# PowerMeter_Peripherics.net
KiCad netlist of a schematic drawn in Altium Designer
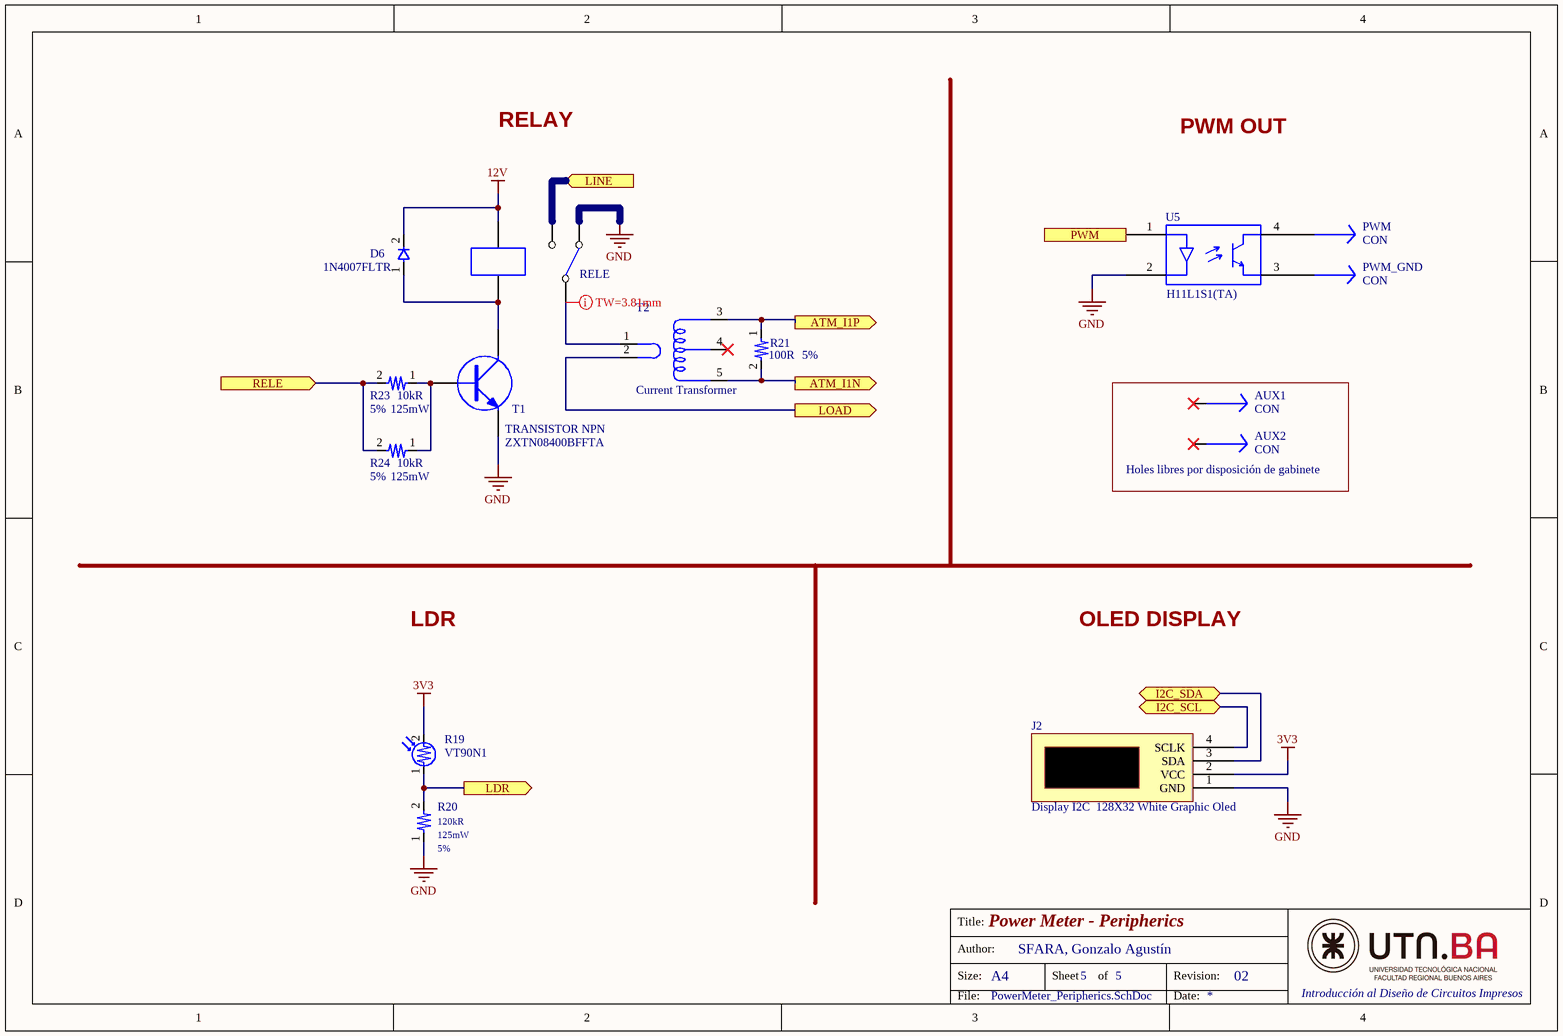
[diagram p0: PowerMeter_Peripherics.SchDoc]

(export (version "E")
  (design (tool "Eeschema 10.0.6"))
  (components
    (comp (ref "AUX1")
      (value "CON")
      (footprint "HOLE 1.3")
      (description "Hole")
      (libsource (lib "PowerMeter") (part "CON"))
    )
    (comp (ref "AUX2")
      (value "CON")
      (footprint "HOLE 1.3")
      (description "Hole")
      (libsource (lib "PowerMeter") (part "CON"))
    )
    (comp (ref "D6")
      (value "Standard Rectifier 1000V SOD-123")
      (footprint "SOD_123")
      (fields
        (field (name "MANUFACTURER") "Sangdest Microelectronics")
        (field (name "MANUFACTURER PART NUMBER") "1N4007FLTR")
      )
      (libsource (lib "PowerMeter") (part "DIODE"))
    )
    (comp (ref "J2")
      (value "Display I2C  128X32 White Graphic Oled")
      (footprint "SSD1306")
      (description "128X32 White Graphic Oled")
      (fields
        (field (name "MANUFACTURER") "Focus LCDs")
        (field (name "MANUFACTURER PART NUMBER") "O12832A-GW-TW3")
      )
      (libsource (lib "PowerMeter") (part "Display I2C"))
    )
    (comp (ref "PWM")
      (value "CON")
      (footprint "HOLE 1.3")
      (description "Hole")
      (libsource (lib "PowerMeter") (part "CON"))
    )
    (comp (ref "PWM_GND")
      (value "CON")
      (footprint "HOLE 1.3")
      (description "Hole")
      (libsource (lib "PowerMeter") (part "CON"))
    )
    (comp (ref "R19")
      (value "LDR 200 Kohm, 80MW")
      (footprint "LDR")
      (description "200 Kohm, 80MW")
      (fields (field (name "MANUFACTURER") "Excelitas") (field (name "MANUFACTURER PART NUMBER") "VT90N1"))
      (libsource (lib "PowerMeter") (part "LDR"))
    )
    (comp (ref "R20")
      (value "RES 120kOhm 5% 1/8W")
      (footprint "R_0805")
      (description "Chip Resistor Automotive Grade Thick Film 0805 120kOhm 5% Paper T/R")
      (fields
        (field (name "MANUFACTURER") "Yageo")
        (field (name "MANUFACTURER PART NUMBER") "AC0805JR-07120KL")
        (field (name "RESISTANCE") "120kR")
        (field (name "TOLERANCE") "5%")
        (field (name "MAX POWER DISSIPATION") "125mW")
      )
      (libsource (lib "PowerMeter") (part "RES"))
    )
    (comp (ref "R21")
      (value "RES 100Ohm 5% 1/8W")
      (footprint "R_0805")
      (description "Anti-Sulfurated Chip Resistor Thick Film 0805 100Ohm 5% Paper T/R")
      (fields
        (field (name "MANUFACTURER") "Yageo")
        (field (name "MANUFACTURER PART NUMBER") "AF0805JR-07100RL")
        (field (name "RESISTANCE") "100R")
        (field (name "TOLERANCE") "5%")
      )
      (libsource (lib "PowerMeter") (part "RES"))
    )
    (comp (ref "R23")
      (value "RES 10kOhm 5% 1/8W")
      (footprint "R_0805")
      (description "Res Thick Film 0805 10K Ohm 5% 1/8W ±200ppm/°C Molded SMD SMD Paper T/R")
      (fields
        (field (name "MANUFACTURER") "Vishay Dale")
        (field (name "MANUFACTURER PART NUMBER") "CRCW080510K0JNEB")
        (field (name "RESISTANCE") "10kR")
        (field (name "TOLERANCE") "5%")
        (field (name "POWER RATING") "125mW")
      )
      (libsource (lib "PowerMeter") (part "RES"))
    )
    (comp (ref "R24")
      (value "RES 10kOhm 5% 1/8W")
      (footprint "R_0805")
      (description "Res Thick Film 0805 10K Ohm 5% 1/8W ±200ppm/°C Molded SMD SMD Paper T/R")
      (fields
        (field (name "MANUFACTURER") "Vishay Dale")
        (field (name "MANUFACTURER PART NUMBER") "CRCW080510K0JNEB")
        (field (name "RESISTANCE") "10kR")
        (field (name "TOLERANCE") "5%")
        (field (name "POWER RATING") "125mW")
      )
      (libsource (lib "PowerMeter") (part "RES"))
    )
    (comp (ref "RELE")
      (value "Relay; 10 A; 12 VDC; PCB; PC Board; SPST-NO; 320 Ohms; 450 mW (Nom.)  T77V1D10-12")
      (footprint "RELE SERIE 964")
      (description "Relay; 10 A; 12 VDC; PCB; PC Board; SPST-NO; 320 Ohms; 450 mW (Nom.)")
      (fields
        (field (name "MANUFACTURER") "TE Connectivity")
        (field (name "MANUFACTURER PART NUMBER") "T77V1D10-12")
      )
      (libsource (lib "PowerMeter") (part "RELE SIMPLE"))
    )
    (comp (ref "T1")
      (value "TRANSISTOR NPN")
      (footprint "SOT23")
      (description "ZXTN08400BFF Series NPN 400 V 500 mA 1.5 W Transistor SMT - SOT-23F")
      (fields
        (field (name "MANUFACTURER") "Diodes Zetex")
        (field (name "MANUFACTURER PART NUMBER") "ZXTN08400BFFTA")
      )
      (libsource (lib "PowerMeter") (part "TRANSISTOR NPN"))
    )
    (comp (ref "T2")
      (value "Current Transformer")
      (footprint "CT")
      (libsource (lib "PowerMeter") (part "CT"))
    )
    (comp (ref "U5")
      (value "OPTOACOPLADOR H11L1S1(TA)")
      (footprint "OPTO GULLWINGx6")
      (description "Optocoupler Logic-Out DC-IN 1-CH 6-Pin SOIC T/R")
      (fields
        (field (name "MANUFACTURER") "Everlight")
        (field (name "MANUFACTURER PART NUMBER") "H11L1S1(TA)")
      )
      (libsource (lib "PowerMeter") (part "OPTOACOPLADOR"))
    )
  )
  (nets
    (net (code "1") (name "/ATM_I1N") (class "Default")
      (node (ref "R21") (pin "2") (pintype "passive"))
      (node (ref "T2") (pin "5") (pinfunction "VN_5") (pintype "passive"))
    )
    (net (code "2") (name "/ATM_I1P") (class "Default")
      (node (ref "R21") (pin "1") (pintype "passive"))
      (node (ref "T2") (pin "3") (pinfunction "VP_3") (pintype "passive"))
    )
    (net (code "3") (name "/I2C_SCL") (class "Default")
      (node (ref "J2") (pin "4") (pinfunction "SCLK_4") (pintype "passive"))
    )
    (net (code "4") (name "/I2C_SDA") (class "Default")
      (node (ref "J2") (pin "3") (pinfunction "SDA_3") (pintype "passive"))
    )
    (net (code "5") (name "/LDR") (class "Default")
      (node (ref "R19") (pin "1") (pintype "passive"))
      (node (ref "R20") (pin "2") (pintype "passive"))
    )
    (net (code "6") (name "/LINE") (class "Default")
      (node (ref "RELE") (pin "NA1") (pinfunction "NA1_NA1") (pintype "passive"))
    )
    (net (code "7") (name "/LOAD") (class "Default")
      (node (ref "T2") (pin "2") (pinfunction "OUT_2") (pintype "passive"))
    )
    (net (code "8") (name "/PWM") (class "Default") (node (ref "U5") (pin "1") (pintype "passive")))
    (net (code "9") (name "/RELE") (class "Default")
      (node (ref "R23") (pin "2") (pintype "passive"))
      (node (ref "R24") (pin "2") (pintype "passive"))
    )
    (net (code "10") (name "3V3") (class "Default")
      (node (ref "J2") (pin "2") (pinfunction "VCC_2") (pintype "power_in"))
      (node (ref "R19") (pin "2") (pintype "passive"))
    )
    (net (code "11") (name "12V") (class "Default")
      (node (ref "D6") (pin "2") (pintype "passive"))
      (node (ref "RELE") (pin "B1") (pinfunction "B1_B1") (pintype "passive"))
    )
    (net (code "12") (name "GND") (class "Default")
      (node (ref "J2") (pin "1") (pinfunction "GND_1") (pintype "power_in"))
      (node (ref "R20") (pin "1") (pintype "passive"))
      (node (ref "RELE") (pin "NC1") (pinfunction "NC1_NC1") (pintype "passive"))
      (node (ref "T1") (pin "3") (pinfunction "E_3") (pintype "passive"))
      (node (ref "U5") (pin "2") (pintype "passive"))
    )
    (net (code "13") (name "Net-(PWM-Pad1)") (class "Default")
      (node (ref "PWM") (pin "1") (pintype "passive"))
      (node (ref "U5") (pin "4") (pintype "passive"))
    )
    (net (code "14") (name "Net-(PWM_GND-Pad1)") (class "Default")
      (node (ref "PWM_GND") (pin "1") (pintype "passive"))
      (node (ref "U5") (pin "3") (pintype "passive"))
    )
    (net (code "15") (name "Net-(T1-B)") (class "Default")
      (node (ref "R23") (pin "1") (pintype "passive"))
      (node (ref "R24") (pin "1") (pintype "passive"))
      (node (ref "T1") (pin "1") (pinfunction "B_1") (pintype "passive"))
    )
    (net (code "16") (name "Net-(T1-C)") (class "Default")
      (node (ref "D6") (pin "1") (pintype "passive"))
      (node (ref "RELE") (pin "B2") (pinfunction "B2_B2") (pintype "passive"))
      (node (ref "T1") (pin "2") (pinfunction "C_2") (pintype "passive"))
    )
    (net (code "17") (name "Net-(T2-IN)") (class "Default")
      (node (ref "RELE") (pin "C1") (pinfunction "C1_C1") (pintype "passive"))
      (node (ref "T2") (pin "1") (pinfunction "IN_1") (pintype "passive"))
    )
    (net (code "18") (name "unconnected-(AUX1-Pad1)") (class "Default")
      (node (ref "AUX1") (pin "1") (pintype "passive+no_connect"))
    )
    (net (code "19") (name "unconnected-(AUX2-Pad1)") (class "Default")
      (node (ref "AUX2") (pin "1") (pintype "passive+no_connect"))
    )
    (net (code "20") (name "unconnected-(T2-MP-Pad4)") (class "Default")
      (node (ref "T2") (pin "4") (pinfunction "MP_4") (pintype "passive+no_connect"))
    )
  )
)
